# AUTOMATIC_WATER_PUMPS_V1.net
KiCad netlist of a schematic drawn in Altium Designer
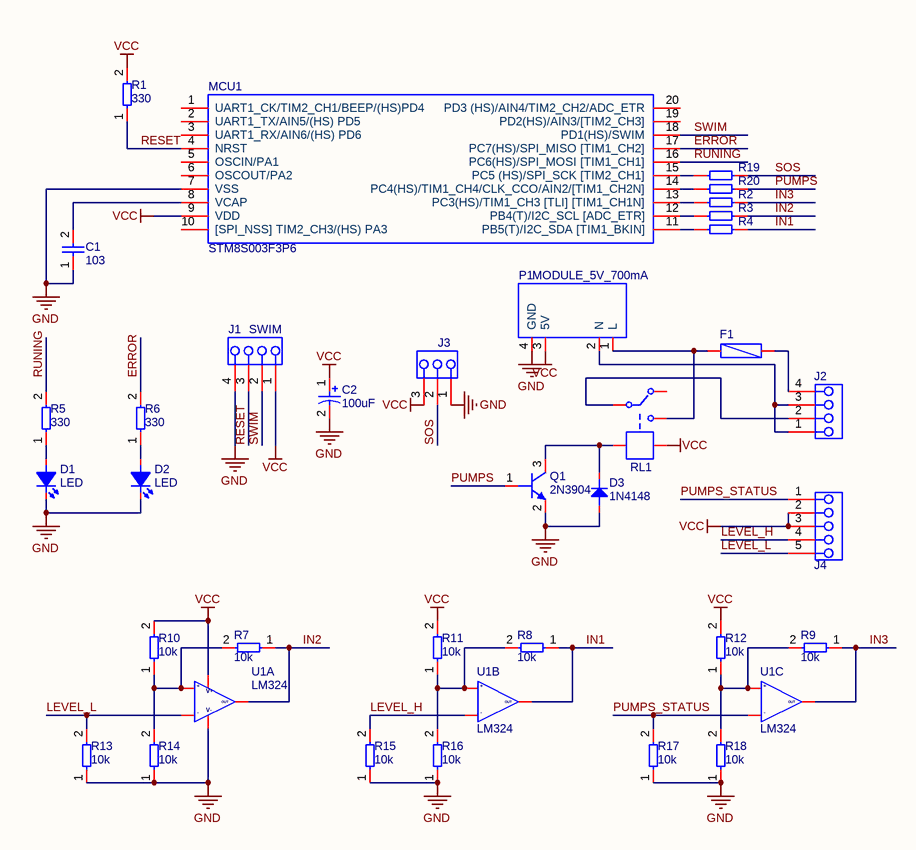
[diagram p0: AUTOMATIC_WATER_PUMPS_V1.SchDoc]

(export (version "E")
  (design (tool "Eeschema 10.0.6"))
  (components
    (comp (ref "C1") (value "103") (footprint "C0805") (libsource (lib "Lib31082020") (part "C0805")))
    (comp (ref "C2")
      (value "100uF")
      (footprint "CAP_RAD_3.5mm")
      (libsource (lib "Lib31082020") (part "Capacitor(Radian)"))
    )
    (comp (ref "D1")
      (value "LED")
      (footprint "LED_3MM_GREEN")
      (libsource (lib "Lib31082020") (part "LED 3MM"))
    )
    (comp (ref "D2")
      (value "LED")
      (footprint "LED_3MM_GREEN")
      (libsource (lib "Lib31082020") (part "LED 3MM"))
    )
    (comp (ref "D3")
      (value "1N4148")
      (footprint "SOD-80")
      (libsource (lib "MyAltiumLibrary") (part "Diode-1N4148"))
    )
    (comp (ref "F1")
      (value "Fuse 5x20mm")
      (footprint "FUSE_5x20MM")
      (libsource (lib "MyAltiumLibrary") (part "Fuse-5x20mm"))
    )
    (comp (ref "J1")
      (value "SWIM")
      (footprint "HEADER-MALE-04PINS-2.54MM")
      (libsource (lib "Lib31082020") (part "HEADER-MALE-04PINS-2.54MM"))
    )
    (comp (ref "J2")
      (value "DEGSON Screws")
      (footprint "DG127-5.0-04P-14-00AH")
      (libsource (lib "Lib31082020") (part "DG127-5.0-04P-14-00AH"))
    )
    (comp (ref "J3")
      (value "SOS")
      (footprint "HEADER-MALE-03PINS-2.54MM")
      (libsource (lib "MyAltiumLibrary") (part "HEADER-MALE-03PINS-2.54MM"))
    )
    (comp (ref "J4")
      (value "DEGSON Screws")
      (footprint "DG127-5.0-05P-14-00AH")
      (libsource (lib "MyAltiumLibrary") (part "DG127-5.0-05P-14-00AH"))
    )
    (comp (ref "MCU1")
      (value "STM8S003F3P6")
      (footprint "TSSOP20_0.65_4.4")
      (libsource (lib "Lib31082020") (part "STM8S003F3P6"))
    )
    (comp (ref "P1")
      (value "MODULE_5V_700mA")
      (footprint "MODULE_5V_700mA")
      (libsource (lib "MyAltiumLibrary") (part "SMPS_5V_700mA"))
    )
    (comp (ref "Q1") (value "2N3904") (footprint "SOT23-3") (libsource (lib "Lib31082020") (part "2N3904")))
    (comp (ref "R1") (value "330") (footprint "R0805") (libsource (lib "") (part "Resistor SMD_1")))
    (comp (ref "R2")
      (value "10k")
      (footprint "R0805")
      (libsource (lib "MyAltiumLibrary") (part "Resistors-SMD"))
    )
    (comp (ref "R3")
      (value "10k")
      (footprint "R0805")
      (libsource (lib "MyAltiumLibrary") (part "Resistors-SMD"))
    )
    (comp (ref "R4")
      (value "10k")
      (footprint "R0805")
      (libsource (lib "MyAltiumLibrary") (part "Resistors-SMD"))
    )
    (comp (ref "R5") (value "330") (footprint "R0805") (libsource (lib "") (part "Resistor SMD_1")))
    (comp (ref "R6") (value "330") (footprint "R0805") (libsource (lib "") (part "Resistor SMD_1")))
    (comp (ref "R7") (value "10k") (footprint "R0805") (libsource (lib "Lib31082020") (part "Resistor SMD")))
    (comp (ref "R8") (value "10k") (footprint "R0805") (libsource (lib "Lib31082020") (part "Resistor SMD")))
    (comp (ref "R9") (value "10k") (footprint "R0805") (libsource (lib "Lib31082020") (part "Resistor SMD")))
    (comp (ref "R10") (value "10k") (footprint "R0805") (libsource (lib "") (part "Resistor SMD_1")))
    (comp (ref "R11") (value "10k") (footprint "R0805") (libsource (lib "") (part "Resistor SMD_1")))
    (comp (ref "R12") (value "10k") (footprint "R0805") (libsource (lib "") (part "Resistor SMD_1")))
    (comp (ref "R13") (value "10k") (footprint "R0805") (libsource (lib "") (part "Resistor SMD_1")))
    (comp (ref "R14") (value "10k") (footprint "R0805") (libsource (lib "") (part "Resistor SMD_1")))
    (comp (ref "R15") (value "10k") (footprint "R0805") (libsource (lib "") (part "Resistor SMD_1")))
    (comp (ref "R16") (value "10k") (footprint "R0805") (libsource (lib "") (part "Resistor SMD_1")))
    (comp (ref "R17") (value "10k") (footprint "R0805") (libsource (lib "") (part "Resistor SMD_1")))
    (comp (ref "R18") (value "10k") (footprint "R0805") (libsource (lib "") (part "Resistor SMD_1")))
    (comp (ref "R19")
      (value "10k")
      (footprint "R0805")
      (libsource (lib "MyAltiumLibrary") (part "Resistors-SMD"))
    )
    (comp (ref "R20")
      (value "10k")
      (footprint "R0805")
      (libsource (lib "MyAltiumLibrary") (part "Resistors-SMD"))
    )
    (comp (ref "RL1")
      (value "RELAY-SONGLE-SRD-05VDC")
      (footprint "RELAY-SONGLE-SRD-05VDC_BLUE")
      (libsource (lib "Lib31082020") (part "RELAY-SONGLE-SRD-05VDC"))
    )
    (comp (ref "U1")
      (value "LM324")
      (footprint "SOP-14")
      (description "Quad-Operational Amp")
      (libsource (lib "Lib31082020") (part "LM324"))
    )
  )
  (nets
    (net (code "1") (name "/ERROR") (class "Default")
      (node (ref "MCU1") (pin "17") (pinfunction "PC7(HS)/SPI_MISO_[TIM1_CH2]_17") (pintype "passive"))
      (node (ref "R6") (pin "2") (pinfunction "2_2") (pintype "passive"))
    )
    (net (code "2") (name "/IN1") (class "Default")
      (node (ref "R4") (pin "2") (pinfunction "2_2") (pintype "passive"))
      (node (ref "R8") (pin "1") (pinfunction "1_1") (pintype "passive"))
      (node (ref "U1") (pin "7") (pinfunction "OUT_7") (pintype "passive"))
    )
    (net (code "3") (name "/IN2") (class "Default")
      (node (ref "R3") (pin "2") (pinfunction "2_2") (pintype "passive"))
      (node (ref "R7") (pin "1") (pinfunction "1_1") (pintype "passive"))
      (node (ref "U1") (pin "1") (pinfunction "OUT_1") (pintype "passive"))
    )
    (net (code "4") (name "/IN3") (class "Default")
      (node (ref "R2") (pin "2") (pinfunction "2_2") (pintype "passive"))
      (node (ref "R9") (pin "1") (pinfunction "1_1") (pintype "passive"))
      (node (ref "U1") (pin "8") (pinfunction "OUT_8") (pintype "passive"))
    )
    (net (code "5") (name "/LEVEL_H") (class "Default")
      (node (ref "J4") (pin "4") (pinfunction "4_4") (pintype "passive"))
      (node (ref "R15") (pin "2") (pinfunction "2_2") (pintype "passive"))
      (node (ref "U1") (pin "6") (pinfunction "-_6") (pintype "passive"))
    )
    (net (code "6") (name "/LEVEL_L") (class "Default")
      (node (ref "J4") (pin "5") (pinfunction "5_5") (pintype "passive"))
      (node (ref "R13") (pin "2") (pinfunction "2_2") (pintype "passive"))
      (node (ref "U1") (pin "2") (pinfunction "-_2") (pintype "passive"))
    )
    (net (code "7") (name "/PUMPS") (class "Default")
      (node (ref "Q1") (pin "1") (pinfunction "B_1") (pintype "passive"))
      (node (ref "R20") (pin "2") (pinfunction "2_2") (pintype "passive"))
    )
    (net (code "8") (name "/PUMPS_STATUS") (class "Default")
      (node (ref "J4") (pin "1") (pinfunction "1_1") (pintype "passive"))
      (node (ref "R17") (pin "2") (pinfunction "2_2") (pintype "passive"))
      (node (ref "U1") (pin "9") (pinfunction "-_9") (pintype "passive"))
    )
    (net (code "9") (name "/RESET") (class "Default")
      (node (ref "J1") (pin "3") (pinfunction "3_3") (pintype "passive"))
      (node (ref "MCU1") (pin "4") (pinfunction "NRST_4") (pintype "passive"))
      (node (ref "R1") (pin "1") (pinfunction "1_1") (pintype "passive"))
    )
    (net (code "10") (name "/RUNING") (class "Default")
      (node (ref "MCU1") (pin "16") (pinfunction "PC6(HS)/SPI_MOSI_[TIM1_CH1]_16") (pintype "passive"))
      (node (ref "R5") (pin "2") (pinfunction "2_2") (pintype "passive"))
    )
    (net (code "11") (name "/SOS") (class "Default")
      (node (ref "J3") (pin "2") (pinfunction "2_2") (pintype "passive"))
      (node (ref "R19") (pin "2") (pinfunction "2_2") (pintype "passive"))
    )
    (net (code "12") (name "/SWIM") (class "Default")
      (node (ref "J1") (pin "2") (pinfunction "2_2") (pintype "passive"))
      (node (ref "MCU1") (pin "18") (pinfunction "PD1(HS)/SWIM_18") (pintype "passive"))
    )
    (net (code "13") (name "GND") (class "Default")
      (node (ref "C1") (pin "1") (pinfunction "1_1") (pintype "passive"))
      (node (ref "C2") (pin "2") (pinfunction "2_2") (pintype "passive"))
      (node (ref "D1") (pin "2") (pinfunction "K_2") (pintype "passive"))
      (node (ref "D2") (pin "2") (pinfunction "K_2") (pintype "passive"))
      (node (ref "D3") (pin "1") (pinfunction "1_1") (pintype "passive"))
      (node (ref "J1") (pin "4") (pinfunction "4_4") (pintype "passive"))
      (node (ref "J3") (pin "1") (pinfunction "1_1") (pintype "passive"))
      (node (ref "MCU1") (pin "7") (pinfunction "VSS_7") (pintype "passive"))
      (node (ref "P1") (pin "4") (pinfunction "GND_4") (pintype "passive"))
      (node (ref "Q1") (pin "2") (pinfunction "E_2") (pintype "passive"))
      (node (ref "R13") (pin "1") (pinfunction "1_1") (pintype "passive"))
      (node (ref "R14") (pin "1") (pinfunction "1_1") (pintype "passive"))
      (node (ref "R15") (pin "1") (pinfunction "1_1") (pintype "passive"))
      (node (ref "R16") (pin "1") (pinfunction "1_1") (pintype "passive"))
      (node (ref "R17") (pin "1") (pinfunction "1_1") (pintype "passive"))
      (node (ref "R18") (pin "1") (pinfunction "1_1") (pintype "passive"))
      (node (ref "U1") (pin "11") (pinfunction "11_11") (pintype "power_in"))
    )
    (net (code "14") (name "Net-(D1-A)") (class "Default")
      (node (ref "D1") (pin "1") (pinfunction "A_1") (pintype "passive"))
      (node (ref "R5") (pin "1") (pinfunction "1_1") (pintype "passive"))
    )
    (net (code "15") (name "Net-(D2-A)") (class "Default")
      (node (ref "D2") (pin "1") (pinfunction "A_1") (pintype "passive"))
      (node (ref "R6") (pin "1") (pinfunction "1_1") (pintype "passive"))
    )
    (net (code "16") (name "Net-(F1-Pad2)") (class "Default")
      (node (ref "F1") (pin "2") (pinfunction "2_2") (pintype "passive"))
      (node (ref "J2") (pin "4") (pinfunction "4_4") (pintype "passive"))
    )
    (net (code "17") (name "Net-(J2-Pad2)") (class "Default")
      (node (ref "J2") (pin "2") (pinfunction "2_2") (pintype "passive"))
      (node (ref "RL1") (pin "2") (pinfunction "2_2") (pintype "passive"))
    )
    (net (code "18") (name "Net-(MCU1-PB4(T){slash}I2C_SCL_[ADC_ETR])") (class "Default")
      (node (ref "MCU1") (pin "12") (pinfunction "PB4(T)/I2C_SCL_[ADC_ETR]_12") (pintype "passive"))
      (node (ref "R3") (pin "1") (pinfunction "1_1") (pintype "passive"))
    )
    (net (code "19") (name "Net-(MCU1-PB5(T){slash}I2C_SDA_[TIM1_BKIN])") (class "Default")
      (node (ref "MCU1") (pin "11") (pinfunction "PB5(T)/I2C_SDA_[TIM1_BKIN]_11") (pintype "passive"))
      (node (ref "R4") (pin "1") (pinfunction "1_1") (pintype "passive"))
    )
    (net (code "20") (name "Net-(MCU1-PC3(HS){slash}TIM1_CH3_[TLI]_[TIM1_CH1N])") (class "Default")
      (node (ref "MCU1") (pin "13") (pinfunction "PC3(HS)/TIM1_CH3_[TLI]_[TIM1_CH1N]_13") (pintype "passive"))
      (node (ref "R2") (pin "1") (pinfunction "1_1") (pintype "passive"))
    )
    (net (code "21") (name "Net-(MCU1-PC4(HS){slash}TIM1_CH4{slash}CLK_CCO{slash}AIN2{slash}[TIM1_CH2N])") (class "Default")
      (node (ref "MCU1") (pin "14") (pinfunction "PC4(HS)/TIM1_CH4/CLK_CCO/AIN2/[TIM1_CH2N]_14") (pintype "passive"))
      (node (ref "R20") (pin "1") (pinfunction "1_1") (pintype "passive"))
    )
    (net (code "22") (name "Net-(MCU1-PC5_(HS){slash}SPI_SCK_[TIM2_CH1])") (class "Default")
      (node (ref "MCU1") (pin "15") (pinfunction "PC5_(HS)/SPI_SCK_[TIM2_CH1]_15") (pintype "passive"))
      (node (ref "R19") (pin "1") (pinfunction "1_1") (pintype "passive"))
    )
    (net (code "23") (name "Net-(MCU1-VCAP)") (class "Default")
      (node (ref "C1") (pin "2") (pinfunction "2_2") (pintype "passive"))
      (node (ref "MCU1") (pin "8") (pinfunction "VCAP_8") (pintype "passive"))
    )
    (net (code "24") (name "Net-(P1-L)") (class "Default")
      (node (ref "F1") (pin "1") (pinfunction "1_1") (pintype "passive"))
      (node (ref "P1") (pin "1") (pinfunction "L_1") (pintype "passive"))
      (node (ref "RL1") (pin "4") (pinfunction "4_4") (pintype "passive"))
    )
    (net (code "25") (name "Net-(P1-N)") (class "Default")
      (node (ref "J2") (pin "1") (pinfunction "1_1") (pintype "passive"))
      (node (ref "J2") (pin "3") (pinfunction "3_3") (pintype "passive"))
      (node (ref "P1") (pin "2") (pinfunction "N_2") (pintype "passive"))
    )
    (net (code "26") (name "Net-(Q1-C)") (class "Default")
      (node (ref "D3") (pin "2") (pinfunction "2_2") (pintype "passive"))
      (node (ref "Q1") (pin "3") (pinfunction "C_3") (pintype "passive"))
      (node (ref "RL1") (pin "1") (pinfunction "1_1") (pintype "passive"))
    )
    (net (code "27") (name "Net-(R11-Pad1)") (class "Default")
      (node (ref "R11") (pin "1") (pinfunction "1_1") (pintype "passive"))
      (node (ref "R16") (pin "2") (pinfunction "2_2") (pintype "passive"))
      (node (ref "R8") (pin "2") (pinfunction "2_2") (pintype "passive"))
      (node (ref "U1") (pin "5") (pinfunction "5_5") (pintype "passive"))
    )
    (net (code "28") (name "Net-(U1A-+)") (class "Default")
      (node (ref "R10") (pin "1") (pinfunction "1_1") (pintype "passive"))
      (node (ref "R14") (pin "2") (pinfunction "2_2") (pintype "passive"))
      (node (ref "R7") (pin "2") (pinfunction "2_2") (pintype "passive"))
      (node (ref "U1") (pin "3") (pinfunction "+_3") (pintype "passive"))
    )
    (net (code "29") (name "Net-(U1C-+)") (class "Default")
      (node (ref "R12") (pin "1") (pinfunction "1_1") (pintype "passive"))
      (node (ref "R18") (pin "2") (pinfunction "2_2") (pintype "passive"))
      (node (ref "R9") (pin "2") (pinfunction "2_2") (pintype "passive"))
      (node (ref "U1") (pin "10") (pinfunction "+_10") (pintype "passive"))
    )
    (net (code "30") (name "VCC") (class "Default")
      (node (ref "C2") (pin "1") (pinfunction "1_1") (pintype "passive"))
      (node (ref "J1") (pin "1") (pinfunction "1_1") (pintype "passive"))
      (node (ref "J3") (pin "3") (pinfunction "3_3") (pintype "passive"))
      (node (ref "J4") (pin "2") (pinfunction "2_2") (pintype "passive"))
      (node (ref "J4") (pin "3") (pinfunction "3_3") (pintype "passive"))
      (node (ref "MCU1") (pin "9") (pinfunction "VDD_9") (pintype "passive"))
      (node (ref "P1") (pin "3") (pinfunction "5V_3") (pintype "passive"))
      (node (ref "R1") (pin "2") (pinfunction "2_2") (pintype "passive"))
      (node (ref "R10") (pin "2") (pinfunction "2_2") (pintype "passive"))
      (node (ref "R11") (pin "2") (pinfunction "2_2") (pintype "passive"))
      (node (ref "R12") (pin "2") (pinfunction "2_2") (pintype "passive"))
      (node (ref "RL1") (pin "3") (pinfunction "3_3") (pintype "passive"))
      (node (ref "U1") (pin "4") (pinfunction "4_4") (pintype "power_in"))
    )
    (net (code "31") (name "unconnected-(MCU1-OSCIN{slash}PA1-Pad5)") (class "Default")
      (node (ref "MCU1") (pin "5") (pinfunction "OSCIN/PA1_5") (pintype "passive"))
    )
    (net (code "32") (name "unconnected-(MCU1-OSCOUT{slash}PA2-Pad6)") (class "Default")
      (node (ref "MCU1") (pin "6") (pinfunction "OSCOUT/PA2_6") (pintype "passive"))
    )
    (net (code "33") (name "unconnected-(MCU1-PD2(HS){slash}AIN3{slash}[TIM2_CH3]-Pad19)") (class "Default")
      (node (ref "MCU1") (pin "19") (pinfunction "PD2(HS)/AIN3/[TIM2_CH3]_19") (pintype "passive"))
    )
    (net (code "34") (name "unconnected-(MCU1-PD3_(HS){slash}AIN4{slash}TIM2_CH2{slash}ADC_ETR-Pad20)") (class "Default")
      (node (ref "MCU1") (pin "20") (pinfunction "PD3_(HS)/AIN4/TIM2_CH2/ADC_ETR_20") (pintype "passive"))
    )
    (net (code "35") (name "unconnected-(MCU1-UART1_CK{slash}TIM2_CH1{slash}BEEP{slash}(HS)PD4-Pad1)") (class "Default")
      (node (ref "MCU1") (pin "1") (pinfunction "UART1_CK/TIM2_CH1/BEEP/(HS)PD4_1") (pintype "passive"))
    )
    (net (code "36") (name "unconnected-(MCU1-UART1_RX{slash}AIN6{slash}(HS)_PD6-Pad3)") (class "Default")
      (node (ref "MCU1") (pin "3") (pinfunction "UART1_RX/AIN6/(HS)_PD6_3") (pintype "passive"))
    )
    (net (code "37") (name "unconnected-(MCU1-UART1_TX{slash}AIN5{slash}(HS)_PD5-Pad2)") (class "Default")
      (node (ref "MCU1") (pin "2") (pinfunction "UART1_TX/AIN5/(HS)_PD5_2") (pintype "passive"))
    )
    (net (code "38") (name "unconnected-(MCU1-[SPI_NSS]_TIM2_CH3{slash}(HS)_PA3-Pad10)") (class "Default")
      (node (ref "MCU1") (pin "10") (pinfunction "[SPI_NSS]_TIM2_CH3/(HS)_PA3_10") (pintype "passive"))
    )
    (net (code "39") (name "unconnected-(RL1-Pad5)") (class "Default")
      (node (ref "RL1") (pin "5") (pinfunction "5_5") (pintype "passive"))
    )
  )
)
